# Mod_Matrix_Mixer_2x4x2.net
KiCad netlist of a schematic drawn in EAGLE
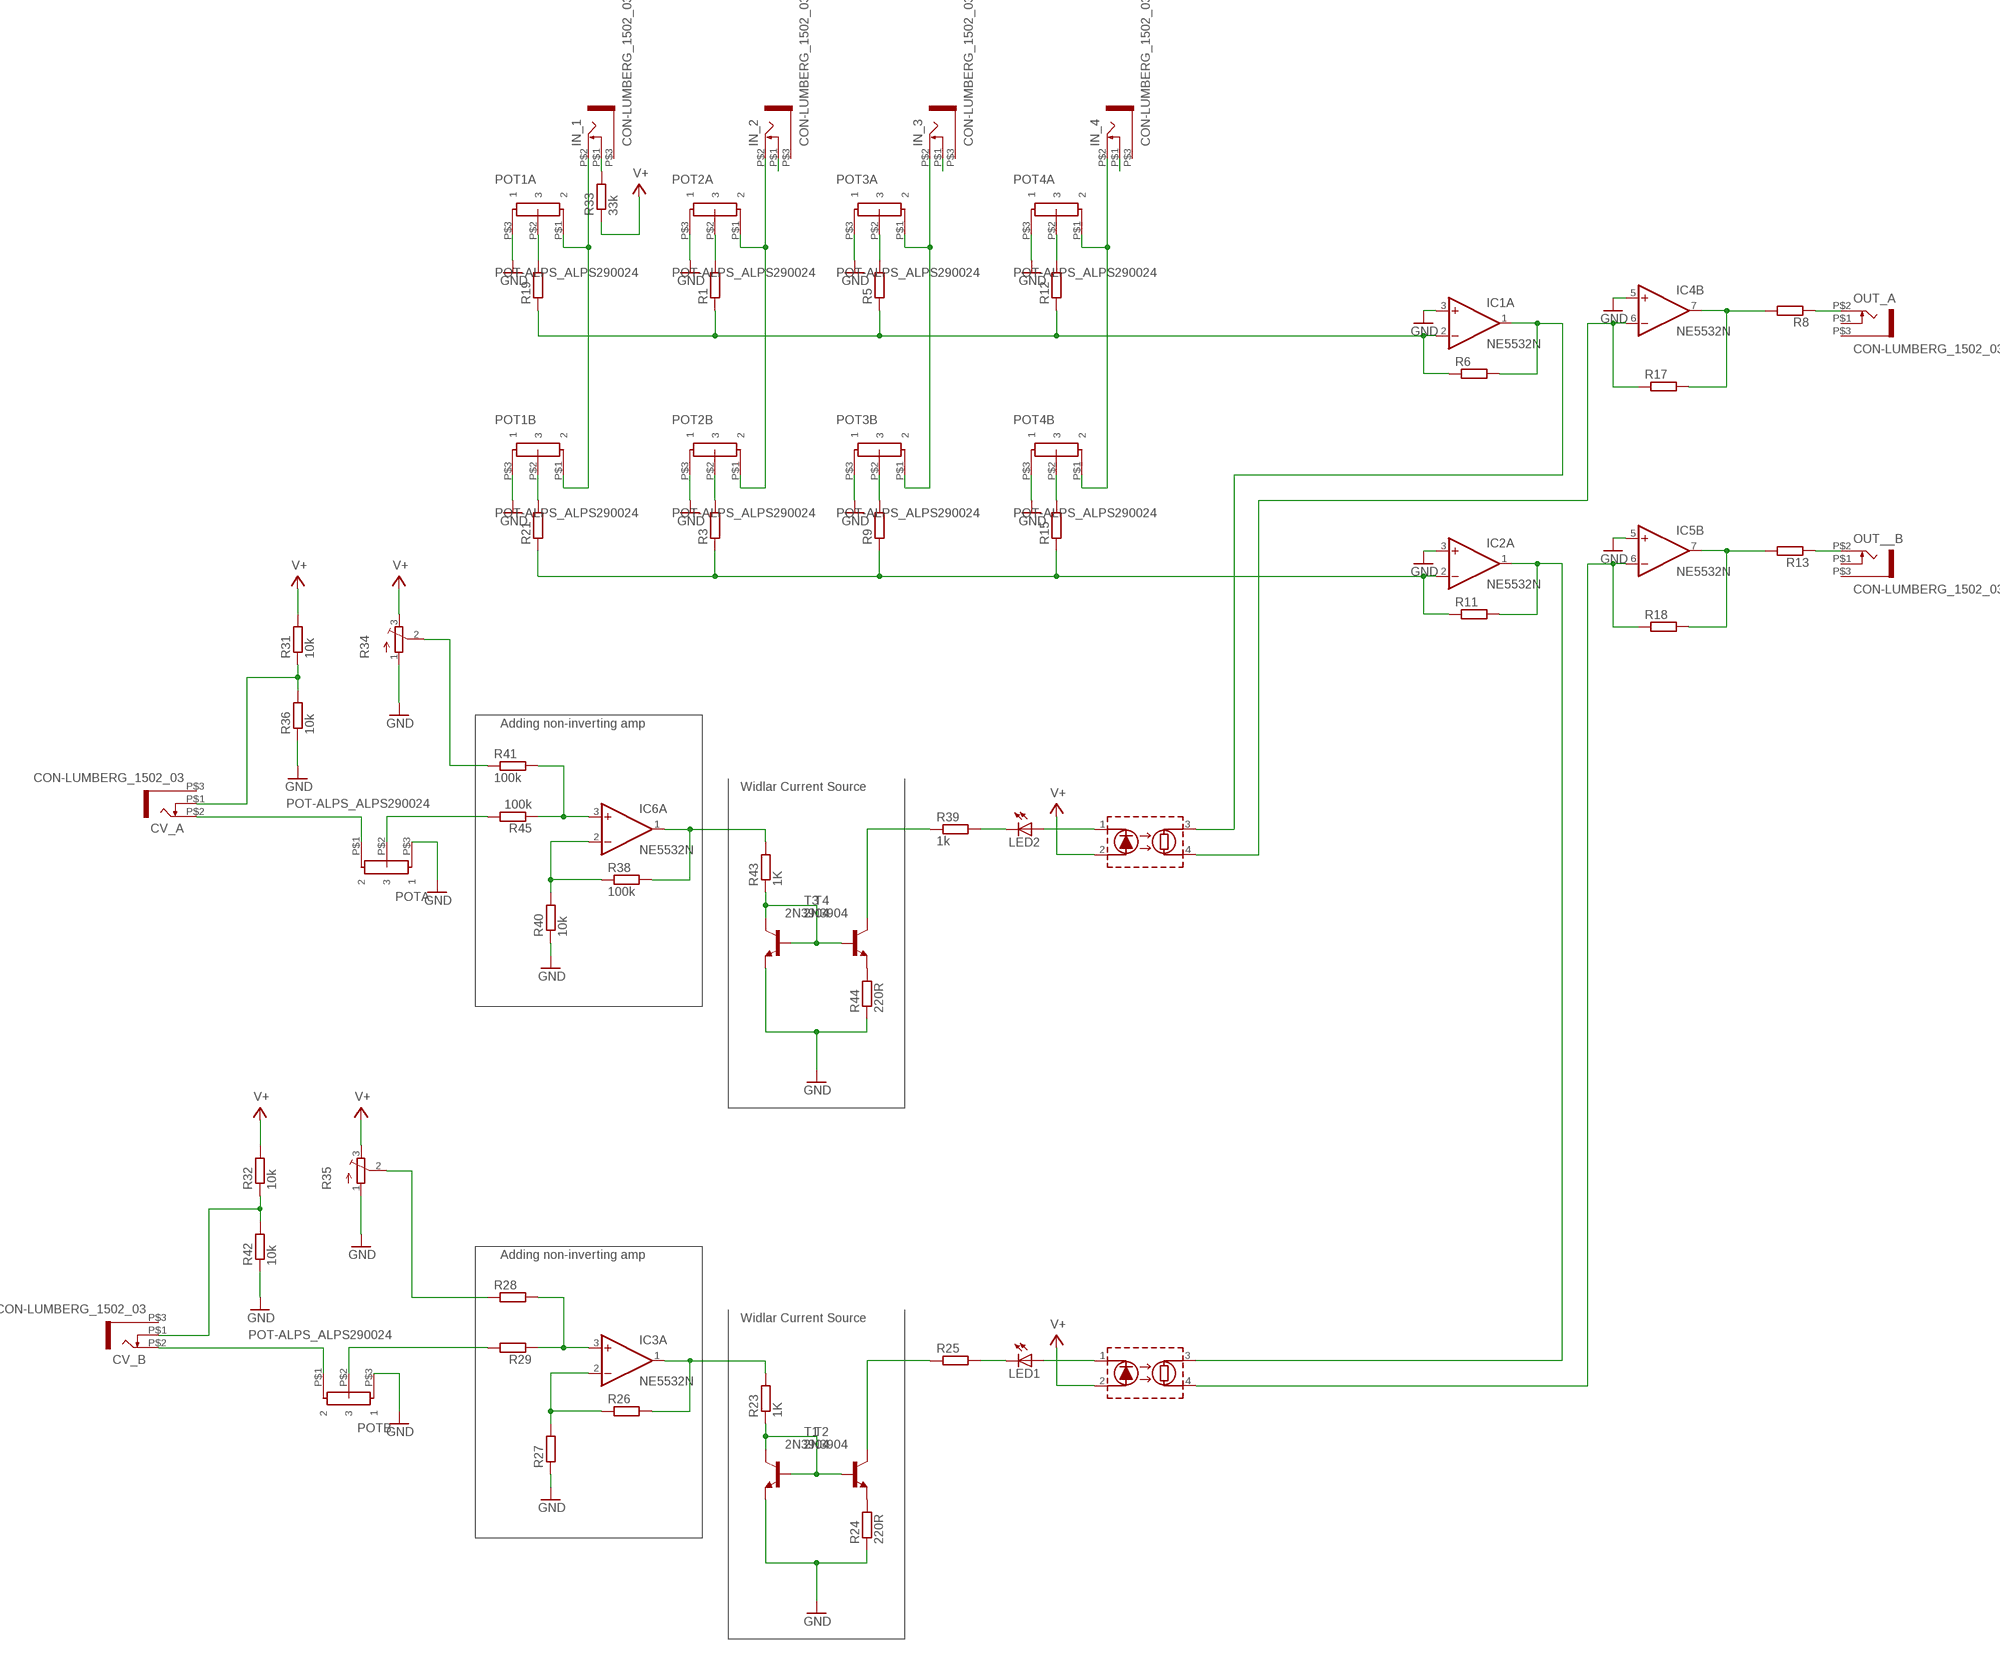
[diagram p0: schematic, sheet 1]

(export (version "E")
  (design (tool "Eeschema 10.0.6"))
  (components
    (comp (ref "CV_A")
      (value "CON-LUMBERG_1502_03")
      (footprint "eagle-import:CON-LUMBERG_1502_03")
      (libsource (lib "eagle-import") (part "CON-LUMBERG_1502_03"))
    )
    (comp (ref "CV_B")
      (value "CON-LUMBERG_1502_03")
      (footprint "eagle-import:CON-LUMBERG_1502_03")
      (libsource (lib "eagle-import") (part "CON-LUMBERG_1502_03"))
    )
    (comp (ref "IC1")
      (value "NE5532N")
      (footprint "eagle-import:DIL08")
      (libsource (lib "eagle-import") (part "NE5532N"))
    )
    (comp (ref "IC2")
      (value "NE5532N")
      (footprint "eagle-import:DIL08")
      (libsource (lib "eagle-import") (part "NE5532N"))
    )
    (comp (ref "IC3")
      (value "NE5532N")
      (footprint "eagle-import:DIL08")
      (libsource (lib "eagle-import") (part "NE5532N"))
    )
    (comp (ref "IC4")
      (value "NE5532N")
      (footprint "eagle-import:DIL08")
      (libsource (lib "eagle-import") (part "NE5532N"))
    )
    (comp (ref "IC5")
      (value "NE5532N")
      (footprint "eagle-import:DIL08")
      (libsource (lib "eagle-import") (part "NE5532N"))
    )
    (comp (ref "IC6")
      (value "NE5532N")
      (footprint "eagle-import:DIL08")
      (libsource (lib "eagle-import") (part "NE5532N"))
    )
    (comp (ref "IN_1")
      (value "CON-LUMBERG_1502_03")
      (footprint "eagle-import:CON-LUMBERG_1502_03")
      (libsource (lib "eagle-import") (part "CON-LUMBERG_1502_03"))
    )
    (comp (ref "IN_2")
      (value "CON-LUMBERG_1502_03")
      (footprint "eagle-import:CON-LUMBERG_1502_03")
      (libsource (lib "eagle-import") (part "CON-LUMBERG_1502_03"))
    )
    (comp (ref "IN_3")
      (value "CON-LUMBERG_1502_03")
      (footprint "eagle-import:CON-LUMBERG_1502_03")
      (libsource (lib "eagle-import") (part "CON-LUMBERG_1502_03"))
    )
    (comp (ref "IN_4")
      (value "CON-LUMBERG_1502_03")
      (footprint "eagle-import:CON-LUMBERG_1502_03")
      (libsource (lib "eagle-import") (part "CON-LUMBERG_1502_03"))
    )
    (comp (ref "LED1")
      (value "LED5MM")
      (footprint "eagle-import:LED5MM")
      (libsource (lib "eagle-import") (part "LED5MM"))
    )
    (comp (ref "LED2")
      (value "LED5MM")
      (footprint "eagle-import:LED5MM")
      (libsource (lib "eagle-import") (part "LED5MM"))
    )
    (comp (ref "OUT_A")
      (value "CON-LUMBERG_1502_03")
      (footprint "eagle-import:CON-LUMBERG_1502_03")
      (libsource (lib "eagle-import") (part "CON-LUMBERG_1502_03"))
    )
    (comp (ref "OUT__B")
      (value "CON-LUMBERG_1502_03")
      (footprint "eagle-import:CON-LUMBERG_1502_03")
      (libsource (lib "eagle-import") (part "CON-LUMBERG_1502_03"))
    )
    (comp (ref "POT1A")
      (value "POT-ALPS_ALPS290024")
      (footprint "eagle-import:POT-ALPS_POT")
      (libsource (lib "eagle-import") (part "POT-ALPS_ALPS290024"))
    )
    (comp (ref "POT1B")
      (value "POT-ALPS_ALPS290024")
      (footprint "eagle-import:POT-ALPS_POT")
      (libsource (lib "eagle-import") (part "POT-ALPS_ALPS290024"))
    )
    (comp (ref "POT2A")
      (value "POT-ALPS_ALPS290024")
      (footprint "eagle-import:POT-ALPS_POT")
      (libsource (lib "eagle-import") (part "POT-ALPS_ALPS290024"))
    )
    (comp (ref "POT2B")
      (value "POT-ALPS_ALPS290024")
      (footprint "eagle-import:POT-ALPS_POT")
      (libsource (lib "eagle-import") (part "POT-ALPS_ALPS290024"))
    )
    (comp (ref "POT3A")
      (value "POT-ALPS_ALPS290024")
      (footprint "eagle-import:POT-ALPS_POT")
      (libsource (lib "eagle-import") (part "POT-ALPS_ALPS290024"))
    )
    (comp (ref "POT3B")
      (value "POT-ALPS_ALPS290024")
      (footprint "eagle-import:POT-ALPS_POT")
      (libsource (lib "eagle-import") (part "POT-ALPS_ALPS290024"))
    )
    (comp (ref "POT4A")
      (value "POT-ALPS_ALPS290024")
      (footprint "eagle-import:POT-ALPS_POT")
      (libsource (lib "eagle-import") (part "POT-ALPS_ALPS290024"))
    )
    (comp (ref "POT4B")
      (value "POT-ALPS_ALPS290024")
      (footprint "eagle-import:POT-ALPS_POT")
      (libsource (lib "eagle-import") (part "POT-ALPS_ALPS290024"))
    )
    (comp (ref "POTA")
      (value "POT-ALPS_ALPS290024")
      (footprint "eagle-import:POT-ALPS_POT")
      (libsource (lib "eagle-import") (part "POT-ALPS_ALPS290024"))
    )
    (comp (ref "POTB")
      (value "POT-ALPS_ALPS290024")
      (footprint "eagle-import:POT-ALPS_POT")
      (libsource (lib "eagle-import") (part "POT-ALPS_ALPS290024"))
    )
    (comp (ref "R1")
      (value "R-EU_0411/15")
      (footprint "eagle-import:0411_15")
      (libsource (lib "eagle-import") (part "R-EU_0411/15"))
    )
    (comp (ref "R3")
      (value "R-EU_0411/15")
      (footprint "eagle-import:0411_15")
      (libsource (lib "eagle-import") (part "R-EU_0411/15"))
    )
    (comp (ref "R5")
      (value "R-EU_0411/15")
      (footprint "eagle-import:0411_15")
      (libsource (lib "eagle-import") (part "R-EU_0411/15"))
    )
    (comp (ref "R6")
      (value "R-EU_0411/15")
      (footprint "eagle-import:0411_15")
      (libsource (lib "eagle-import") (part "R-EU_0411/15"))
    )
    (comp (ref "R8")
      (value "R-EU_0411/15")
      (footprint "eagle-import:0411_15")
      (libsource (lib "eagle-import") (part "R-EU_0411/15"))
    )
    (comp (ref "R9")
      (value "R-EU_0411/15")
      (footprint "eagle-import:0411_15")
      (libsource (lib "eagle-import") (part "R-EU_0411/15"))
    )
    (comp (ref "R11")
      (value "R-EU_0411/15")
      (footprint "eagle-import:0411_15")
      (libsource (lib "eagle-import") (part "R-EU_0411/15"))
    )
    (comp (ref "R12")
      (value "R-EU_0411/15")
      (footprint "eagle-import:0411_15")
      (libsource (lib "eagle-import") (part "R-EU_0411/15"))
    )
    (comp (ref "R13")
      (value "R-EU_0411/15")
      (footprint "eagle-import:0411_15")
      (libsource (lib "eagle-import") (part "R-EU_0411/15"))
    )
    (comp (ref "R15")
      (value "R-EU_0411/15")
      (footprint "eagle-import:0411_15")
      (libsource (lib "eagle-import") (part "R-EU_0411/15"))
    )
    (comp (ref "R17")
      (value "R-EU_0411/15")
      (footprint "eagle-import:0411_15")
      (libsource (lib "eagle-import") (part "R-EU_0411/15"))
    )
    (comp (ref "R18")
      (value "R-EU_0411/15")
      (footprint "eagle-import:0411_15")
      (libsource (lib "eagle-import") (part "R-EU_0411/15"))
    )
    (comp (ref "R19")
      (value "R-EU_0411/15")
      (footprint "eagle-import:0411_15")
      (libsource (lib "eagle-import") (part "R-EU_0411/15"))
    )
    (comp (ref "R21")
      (value "R-EU_0411/15")
      (footprint "eagle-import:0411_15")
      (libsource (lib "eagle-import") (part "R-EU_0411/15"))
    )
    (comp (ref "R23")
      (value "1K")
      (footprint "eagle-import:0411_15")
      (libsource (lib "eagle-import") (part "R-EU_0411/15"))
    )
    (comp (ref "R24")
      (value "220R")
      (footprint "eagle-import:0411_15")
      (libsource (lib "eagle-import") (part "R-EU_0411/15"))
    )
    (comp (ref "R25")
      (value "R-EU_0411/15")
      (footprint "eagle-import:0411_15")
      (libsource (lib "eagle-import") (part "R-EU_0411/15"))
    )
    (comp (ref "R26")
      (value "R-EU_0411/15")
      (footprint "eagle-import:0411_15")
      (libsource (lib "eagle-import") (part "R-EU_0411/15"))
    )
    (comp (ref "R27")
      (value "R-EU_0411/15")
      (footprint "eagle-import:0411_15")
      (libsource (lib "eagle-import") (part "R-EU_0411/15"))
    )
    (comp (ref "R28")
      (value "R-EU_0411/15")
      (footprint "eagle-import:0411_15")
      (libsource (lib "eagle-import") (part "R-EU_0411/15"))
    )
    (comp (ref "R29")
      (value "R-EU_0411/15")
      (footprint "eagle-import:0411_15")
      (libsource (lib "eagle-import") (part "R-EU_0411/15"))
    )
    (comp (ref "R31")
      (value "10k")
      (footprint "eagle-import:0411_15")
      (libsource (lib "eagle-import") (part "R-EU_0411/15"))
    )
    (comp (ref "R32")
      (value "10k")
      (footprint "eagle-import:0411_15")
      (libsource (lib "eagle-import") (part "R-EU_0411/15"))
    )
    (comp (ref "R33")
      (value "33k")
      (footprint "eagle-import:0411_15")
      (libsource (lib "eagle-import") (part "R-EU_0411/15"))
    )
    (comp (ref "R34")
      (value "TRIM_EU-3223W")
      (footprint "eagle-import:3223W")
      (libsource (lib "eagle-import") (part "TRIM_EU-3223W"))
    )
    (comp (ref "R35")
      (value "TRIM_EU-3223W")
      (footprint "eagle-import:3223W")
      (libsource (lib "eagle-import") (part "TRIM_EU-3223W"))
    )
    (comp (ref "R36")
      (value "10k")
      (footprint "eagle-import:0411_15")
      (libsource (lib "eagle-import") (part "R-EU_0411/15"))
    )
    (comp (ref "R38")
      (value "100k")
      (footprint "eagle-import:0411_15")
      (libsource (lib "eagle-import") (part "R-EU_0411/15"))
    )
    (comp (ref "R39")
      (value "1k")
      (footprint "eagle-import:0411_15")
      (libsource (lib "eagle-import") (part "R-EU_0411/15"))
    )
    (comp (ref "R40")
      (value "10k")
      (footprint "eagle-import:0411_15")
      (libsource (lib "eagle-import") (part "R-EU_0411/15"))
    )
    (comp (ref "R41")
      (value "100k")
      (footprint "eagle-import:0411_15")
      (libsource (lib "eagle-import") (part "R-EU_0411/15"))
    )
    (comp (ref "R42")
      (value "10k")
      (footprint "eagle-import:0411_15")
      (libsource (lib "eagle-import") (part "R-EU_0411/15"))
    )
    (comp (ref "R43")
      (value "1K")
      (footprint "eagle-import:0411_15")
      (libsource (lib "eagle-import") (part "R-EU_0411/15"))
    )
    (comp (ref "R44")
      (value "220R")
      (footprint "eagle-import:0411_15")
      (libsource (lib "eagle-import") (part "R-EU_0411/15"))
    )
    (comp (ref "R45")
      (value "100k")
      (footprint "eagle-import:0411_15")
      (libsource (lib "eagle-import") (part "R-EU_0411/15"))
    )
    (comp (ref "T1")
      (value "2N3904")
      (footprint "eagle-import:TO92")
      (libsource (lib "eagle-import") (part "2N3904"))
    )
    (comp (ref "T2")
      (value "2N3904")
      (footprint "eagle-import:TO92")
      (libsource (lib "eagle-import") (part "2N3904"))
    )
    (comp (ref "T3")
      (value "2N3904")
      (footprint "eagle-import:TO92")
      (libsource (lib "eagle-import") (part "2N3904"))
    )
    (comp (ref "T4")
      (value "2N3904")
      (footprint "eagle-import:TO92")
      (libsource (lib "eagle-import") (part "2N3904"))
    )
    (comp (ref "U$1")
      (value "VTL5C3")
      (footprint "eagle-import:VTL5C3")
      (libsource (lib "eagle-import") (part "VTL5C3"))
    )
    (comp (ref "U$2")
      (value "VTL5C3")
      (footprint "eagle-import:VTL5C3")
      (libsource (lib "eagle-import") (part "VTL5C3"))
    )
  )
  (nets
    (net (code "1") (name "GND") (class "Default")
      (node (ref "IC1") (pin "3") (pinfunction "+IN_3") (pintype "input"))
      (node (ref "IC2") (pin "3") (pinfunction "+IN_3") (pintype "input"))
      (node (ref "IC4") (pin "5") (pinfunction "+IN_5") (pintype "input"))
      (node (ref "IC5") (pin "5") (pinfunction "+IN_5") (pintype "input"))
      (node (ref "POT1A") (pin "P$3") (pinfunction "1_P$3") (pintype "bidirectional"))
      (node (ref "POT1B") (pin "P$3") (pinfunction "1_P$3") (pintype "bidirectional"))
      (node (ref "POT2A") (pin "P$3") (pinfunction "1_P$3") (pintype "bidirectional"))
      (node (ref "POT2B") (pin "P$3") (pinfunction "1_P$3") (pintype "bidirectional"))
      (node (ref "POT3A") (pin "P$3") (pinfunction "1_P$3") (pintype "bidirectional"))
      (node (ref "POT3B") (pin "P$3") (pinfunction "1_P$3") (pintype "bidirectional"))
      (node (ref "POT4A") (pin "P$3") (pinfunction "1_P$3") (pintype "bidirectional"))
      (node (ref "POT4B") (pin "P$3") (pinfunction "1_P$3") (pintype "bidirectional"))
      (node (ref "POTA") (pin "P$3") (pinfunction "1_P$3") (pintype "bidirectional"))
      (node (ref "POTB") (pin "P$3") (pinfunction "1_P$3") (pintype "bidirectional"))
      (node (ref "R24") (pin "1") (pinfunction "1_1") (pintype "passive"))
      (node (ref "R27") (pin "1") (pinfunction "1_1") (pintype "passive"))
      (node (ref "R34") (pin "1") (pinfunction "A_1") (pintype "passive"))
      (node (ref "R35") (pin "1") (pinfunction "A_1") (pintype "passive"))
      (node (ref "R36") (pin "1") (pinfunction "1_1") (pintype "passive"))
      (node (ref "R40") (pin "1") (pinfunction "1_1") (pintype "passive"))
      (node (ref "R42") (pin "1") (pinfunction "1_1") (pintype "passive"))
      (node (ref "R44") (pin "1") (pinfunction "1_1") (pintype "passive"))
      (node (ref "T2") (pin "3") (pinfunction "E_3") (pintype "passive"))
      (node (ref "T4") (pin "3") (pinfunction "E_3") (pintype "passive"))
    )
    (net (code "2") (name "Net-(CV_A-3)") (class "Default")
      (node (ref "CV_A") (pin "P$2") (pinfunction "3_P$2") (pintype "passive"))
      (node (ref "POTA") (pin "P$1") (pinfunction "2_P$1") (pintype "bidirectional"))
    )
    (net (code "3") (name "Net-(CV_A-4)") (class "Default")
      (node (ref "CV_A") (pin "P$1") (pinfunction "4_P$1") (pintype "passive"))
      (node (ref "R31") (pin "1") (pinfunction "1_1") (pintype "passive"))
      (node (ref "R36") (pin "2") (pinfunction "2_2") (pintype "passive"))
    )
    (net (code "4") (name "Net-(CV_B-3)") (class "Default")
      (node (ref "CV_B") (pin "P$2") (pinfunction "3_P$2") (pintype "passive"))
      (node (ref "POTB") (pin "P$1") (pinfunction "2_P$1") (pintype "bidirectional"))
    )
    (net (code "5") (name "Net-(CV_B-4)") (class "Default")
      (node (ref "CV_B") (pin "P$1") (pinfunction "4_P$1") (pintype "passive"))
      (node (ref "R32") (pin "1") (pinfunction "1_1") (pintype "passive"))
      (node (ref "R42") (pin "2") (pinfunction "2_2") (pintype "passive"))
    )
    (net (code "6") (name "Net-(IC1A--IN)") (class "Default")
      (node (ref "IC1") (pin "2") (pinfunction "-IN_2") (pintype "input"))
      (node (ref "R1") (pin "1") (pinfunction "1_1") (pintype "passive"))
      (node (ref "R12") (pin "1") (pinfunction "1_1") (pintype "passive"))
      (node (ref "R19") (pin "1") (pinfunction "1_1") (pintype "passive"))
      (node (ref "R5") (pin "1") (pinfunction "1_1") (pintype "passive"))
      (node (ref "R6") (pin "1") (pinfunction "1_1") (pintype "passive"))
    )
    (net (code "7") (name "Net-(IC1A-OUT)") (class "Default")
      (node (ref "IC1") (pin "1") (pinfunction "OUT_1") (pintype "output"))
      (node (ref "R6") (pin "2") (pinfunction "2_2") (pintype "passive"))
      (node (ref "U$2") (pin "3") (pinfunction "LDRA_3") (pintype "bidirectional"))
    )
    (net (code "8") (name "Net-(IC2A--IN)") (class "Default")
      (node (ref "IC2") (pin "2") (pinfunction "-IN_2") (pintype "input"))
      (node (ref "R11") (pin "1") (pinfunction "1_1") (pintype "passive"))
      (node (ref "R15") (pin "1") (pinfunction "1_1") (pintype "passive"))
      (node (ref "R21") (pin "1") (pinfunction "1_1") (pintype "passive"))
      (node (ref "R3") (pin "1") (pinfunction "1_1") (pintype "passive"))
      (node (ref "R9") (pin "1") (pinfunction "1_1") (pintype "passive"))
    )
    (net (code "9") (name "Net-(IC2A-OUT)") (class "Default")
      (node (ref "IC2") (pin "1") (pinfunction "OUT_1") (pintype "output"))
      (node (ref "R11") (pin "2") (pinfunction "2_2") (pintype "passive"))
      (node (ref "U$1") (pin "3") (pinfunction "LDRA_3") (pintype "bidirectional"))
    )
    (net (code "10") (name "Net-(IC3A-+IN)") (class "Default")
      (node (ref "IC3") (pin "3") (pinfunction "+IN_3") (pintype "input"))
      (node (ref "R28") (pin "2") (pinfunction "2_2") (pintype "passive"))
      (node (ref "R29") (pin "1") (pinfunction "1_1") (pintype "passive"))
    )
    (net (code "11") (name "Net-(IC3A--IN)") (class "Default")
      (node (ref "IC3") (pin "2") (pinfunction "-IN_2") (pintype "input"))
      (node (ref "R26") (pin "1") (pinfunction "1_1") (pintype "passive"))
      (node (ref "R27") (pin "2") (pinfunction "2_2") (pintype "passive"))
    )
    (net (code "12") (name "Net-(IC3A-OUT)") (class "Default")
      (node (ref "IC3") (pin "1") (pinfunction "OUT_1") (pintype "output"))
      (node (ref "R23") (pin "2") (pinfunction "2_2") (pintype "passive"))
      (node (ref "R26") (pin "2") (pinfunction "2_2") (pintype "passive"))
    )
    (net (code "13") (name "Net-(IC4B--IN)") (class "Default")
      (node (ref "IC4") (pin "6") (pinfunction "-IN_6") (pintype "input"))
      (node (ref "R17") (pin "1") (pinfunction "1_1") (pintype "passive"))
      (node (ref "U$2") (pin "4") (pinfunction "LDRB_4") (pintype "bidirectional"))
    )
    (net (code "14") (name "Net-(IC4B-OUT)") (class "Default")
      (node (ref "IC4") (pin "7") (pinfunction "OUT_7") (pintype "output"))
      (node (ref "R17") (pin "2") (pinfunction "2_2") (pintype "passive"))
      (node (ref "R8") (pin "2") (pinfunction "2_2") (pintype "passive"))
    )
    (net (code "15") (name "Net-(IC5B--IN)") (class "Default")
      (node (ref "IC5") (pin "6") (pinfunction "-IN_6") (pintype "input"))
      (node (ref "R18") (pin "1") (pinfunction "1_1") (pintype "passive"))
      (node (ref "U$1") (pin "4") (pinfunction "LDRB_4") (pintype "bidirectional"))
    )
    (net (code "16") (name "Net-(IC5B-OUT)") (class "Default")
      (node (ref "IC5") (pin "7") (pinfunction "OUT_7") (pintype "output"))
      (node (ref "R13") (pin "2") (pinfunction "2_2") (pintype "passive"))
      (node (ref "R18") (pin "2") (pinfunction "2_2") (pintype "passive"))
    )
    (net (code "17") (name "Net-(IC6A-+IN)") (class "Default")
      (node (ref "IC6") (pin "3") (pinfunction "+IN_3") (pintype "input"))
      (node (ref "R41") (pin "2") (pinfunction "2_2") (pintype "passive"))
      (node (ref "R45") (pin "1") (pinfunction "1_1") (pintype "passive"))
    )
    (net (code "18") (name "Net-(IC6A--IN)") (class "Default")
      (node (ref "IC6") (pin "2") (pinfunction "-IN_2") (pintype "input"))
      (node (ref "R38") (pin "1") (pinfunction "1_1") (pintype "passive"))
      (node (ref "R40") (pin "2") (pinfunction "2_2") (pintype "passive"))
    )
    (net (code "19") (name "Net-(IC6A-OUT)") (class "Default")
      (node (ref "IC6") (pin "1") (pinfunction "OUT_1") (pintype "output"))
      (node (ref "R38") (pin "2") (pinfunction "2_2") (pintype "passive"))
      (node (ref "R43") (pin "2") (pinfunction "2_2") (pintype "passive"))
    )
    (net (code "20") (name "Net-(IN_1-3)") (class "Default")
      (node (ref "IN_1") (pin "P$2") (pinfunction "3_P$2") (pintype "passive"))
      (node (ref "POT1A") (pin "P$1") (pinfunction "2_P$1") (pintype "bidirectional"))
      (node (ref "POT1B") (pin "P$1") (pinfunction "2_P$1") (pintype "bidirectional"))
    )
    (net (code "21") (name "Net-(IN_1-4)") (class "Default")
      (node (ref "IN_1") (pin "P$1") (pinfunction "4_P$1") (pintype "passive"))
      (node (ref "R33") (pin "2") (pinfunction "2_2") (pintype "passive"))
    )
    (net (code "22") (name "Net-(IN_2-3)") (class "Default")
      (node (ref "IN_2") (pin "P$2") (pinfunction "3_P$2") (pintype "passive"))
      (node (ref "POT2A") (pin "P$1") (pinfunction "2_P$1") (pintype "bidirectional"))
      (node (ref "POT2B") (pin "P$1") (pinfunction "2_P$1") (pintype "bidirectional"))
    )
    (net (code "23") (name "Net-(IN_3-3)") (class "Default")
      (node (ref "IN_3") (pin "P$2") (pinfunction "3_P$2") (pintype "passive"))
      (node (ref "POT3A") (pin "P$1") (pinfunction "2_P$1") (pintype "bidirectional"))
      (node (ref "POT3B") (pin "P$1") (pinfunction "2_P$1") (pintype "bidirectional"))
    )
    (net (code "24") (name "Net-(IN_4-3)") (class "Default")
      (node (ref "IN_4") (pin "P$2") (pinfunction "3_P$2") (pintype "passive"))
      (node (ref "POT4A") (pin "P$1") (pinfunction "2_P$1") (pintype "bidirectional"))
      (node (ref "POT4B") (pin "P$1") (pinfunction "2_P$1") (pintype "bidirectional"))
    )
    (net (code "25") (name "Net-(LED1-C)") (class "Default")
      (node (ref "LED1") (pin "K") (pinfunction "C_K") (pintype "passive"))
      (node (ref "R25") (pin "2") (pinfunction "2_2") (pintype "passive"))
    )
    (net (code "26") (name "Net-(LED2-C)") (class "Default")
      (node (ref "LED2") (pin "K") (pinfunction "C_K") (pintype "passive"))
      (node (ref "R39") (pin "2") (pinfunction "2_2") (pintype "passive"))
    )
    (net (code "27") (name "Net-(OUT_A-3)") (class "Default")
      (node (ref "OUT_A") (pin "P$2") (pinfunction "3_P$2") (pintype "passive"))
      (node (ref "R8") (pin "1") (pinfunction "1_1") (pintype "passive"))
    )
    (net (code "28") (name "Net-(OUT__B-3)") (class "Default")
      (node (ref "OUT__B") (pin "P$2") (pinfunction "3_P$2") (pintype "passive"))
      (node (ref "R13") (pin "1") (pinfunction "1_1") (pintype "passive"))
    )
    (net (code "29") (name "Net-(POT1A-3)") (class "Default")
      (node (ref "POT1A") (pin "P$2") (pinfunction "3_P$2") (pintype "bidirectional"))
      (node (ref "R19") (pin "2") (pinfunction "2_2") (pintype "passive"))
    )
    (net (code "30") (name "Net-(POT1B-3)") (class "Default")
      (node (ref "POT1B") (pin "P$2") (pinfunction "3_P$2") (pintype "bidirectional"))
      (node (ref "R21") (pin "2") (pinfunction "2_2") (pintype "passive"))
    )
    (net (code "31") (name "Net-(POT2A-3)") (class "Default")
      (node (ref "POT2A") (pin "P$2") (pinfunction "3_P$2") (pintype "bidirectional"))
      (node (ref "R1") (pin "2") (pinfunction "2_2") (pintype "passive"))
    )
    (net (code "32") (name "Net-(POT2B-3)") (class "Default")
      (node (ref "POT2B") (pin "P$2") (pinfunction "3_P$2") (pintype "bidirectional"))
      (node (ref "R3") (pin "2") (pinfunction "2_2") (pintype "passive"))
    )
    (net (code "33") (name "Net-(POT3A-3)") (class "Default")
      (node (ref "POT3A") (pin "P$2") (pinfunction "3_P$2") (pintype "bidirectional"))
      (node (ref "R5") (pin "2") (pinfunction "2_2") (pintype "passive"))
    )
    (net (code "34") (name "Net-(POT3B-3)") (class "Default")
      (node (ref "POT3B") (pin "P$2") (pinfunction "3_P$2") (pintype "bidirectional"))
      (node (ref "R9") (pin "2") (pinfunction "2_2") (pintype "passive"))
    )
    (net (code "35") (name "Net-(POT4A-3)") (class "Default")
      (node (ref "POT4A") (pin "P$2") (pinfunction "3_P$2") (pintype "bidirectional"))
      (node (ref "R12") (pin "2") (pinfunction "2_2") (pintype "passive"))
    )
    (net (code "36") (name "Net-(POT4B-3)") (class "Default")
      (node (ref "POT4B") (pin "P$2") (pinfunction "3_P$2") (pintype "bidirectional"))
      (node (ref "R15") (pin "2") (pinfunction "2_2") (pintype "passive"))
    )
    (net (code "37") (name "Net-(POTA-3)") (class "Default")
      (node (ref "POTA") (pin "P$2") (pinfunction "3_P$2") (pintype "bidirectional"))
      (node (ref "R45") (pin "2") (pinfunction "2_2") (pintype "passive"))
    )
    (net (code "38") (name "Net-(POTB-3)") (class "Default")
      (node (ref "POTB") (pin "P$2") (pinfunction "3_P$2") (pintype "bidirectional"))
      (node (ref "R29") (pin "2") (pinfunction "2_2") (pintype "passive"))
    )
    (net (code "39") (name "Net-(R34-S)") (class "Default")
      (node (ref "R34") (pin "2") (pinfunction "S_2") (pintype "passive"))
      (node (ref "R41") (pin "1") (pinfunction "1_1") (pintype "passive"))
    )
    (net (code "40") (name "Net-(R35-S)") (class "Default")
      (node (ref "R28") (pin "1") (pinfunction "1_1") (pintype "passive"))
      (node (ref "R35") (pin "2") (pinfunction "S_2") (pintype "passive"))
    )
    (net (code "41") (name "Net-(T1-B)") (class "Default")
      (node (ref "R23") (pin "1") (pinfunction "1_1") (pintype "passive"))
      (node (ref "T1") (pin "2") (pinfunction "B_2") (pintype "passive"))
      (node (ref "T2") (pin "1") (pinfunction "C_1") (pintype "passive"))
      (node (ref "T2") (pin "2") (pinfunction "B_2") (pintype "passive"))
    )
    (net (code "42") (name "Net-(T1-C)") (class "Default")
      (node (ref "R25") (pin "1") (pinfunction "1_1") (pintype "passive"))
      (node (ref "T1") (pin "1") (pinfunction "C_1") (pintype "passive"))
    )
    (net (code "43") (name "Net-(T1-E)") (class "Default")
      (node (ref "R24") (pin "2") (pinfunction "2_2") (pintype "passive"))
      (node (ref "T1") (pin "3") (pinfunction "E_3") (pintype "passive"))
    )
    (net (code "44") (name "Net-(T3-B)") (class "Default")
      (node (ref "R43") (pin "1") (pinfunction "1_1") (pintype "passive"))
      (node (ref "T3") (pin "2") (pinfunction "B_2") (pintype "passive"))
      (node (ref "T4") (pin "1") (pinfunction "C_1") (pintype "passive"))
      (node (ref "T4") (pin "2") (pinfunction "B_2") (pintype "passive"))
    )
    (net (code "45") (name "Net-(T3-C)") (class "Default")
      (node (ref "R39") (pin "1") (pinfunction "1_1") (pintype "passive"))
      (node (ref "T3") (pin "1") (pinfunction "C_1") (pintype "passive"))
    )
    (net (code "46") (name "Net-(T3-E)") (class "Default")
      (node (ref "R44") (pin "2") (pinfunction "2_2") (pintype "passive"))
      (node (ref "T3") (pin "3") (pinfunction "E_3") (pintype "passive"))
    )
    (net (code "47") (name "Net-(U$1-LED-)") (class "Default")
      (node (ref "LED1") (pin "A") (pinfunction "A_A") (pintype "passive"))
      (node (ref "U$1") (pin "1") (pinfunction "LED-_1") (pintype "bidirectional"))
    )
    (net (code "48") (name "Net-(U$2-LED-)") (class "Default")
      (node (ref "LED2") (pin "A") (pinfunction "A_A") (pintype "passive"))
      (node (ref "U$2") (pin "1") (pinfunction "LED-_1") (pintype "bidirectional"))
    )
    (net (code "49") (name "V+") (class "Default")
      (node (ref "R31") (pin "2") (pinfunction "2_2") (pintype "passive"))
      (node (ref "R32") (pin "2") (pinfunction "2_2") (pintype "passive"))
      (node (ref "R33") (pin "1") (pinfunction "1_1") (pintype "passive"))
      (node (ref "R34") (pin "3") (pinfunction "E_3") (pintype "passive"))
      (node (ref "R35") (pin "3") (pinfunction "E_3") (pintype "passive"))
      (node (ref "U$1") (pin "2") (pinfunction "LED+_2") (pintype "bidirectional"))
      (node (ref "U$2") (pin "2") (pinfunction "LED+_2") (pintype "bidirectional"))
    )
    (net (code "50") (name "unconnected-(CV_A-5-PadP$3)") (class "Default")
      (node (ref "CV_A") (pin "P$3") (pinfunction "5_P$3") (pintype "passive"))
    )
    (net (code "51") (name "unconnected-(CV_B-5-PadP$3)") (class "Default")
      (node (ref "CV_B") (pin "P$3") (pinfunction "5_P$3") (pintype "passive"))
    )
    (net (code "52") (name "unconnected-(IN_1-5-PadP$3)") (class "Default")
      (node (ref "IN_1") (pin "P$3") (pinfunction "5_P$3") (pintype "passive"))
    )
    (net (code "53") (name "unconnected-(IN_2-4-PadP$1)") (class "Default")
      (node (ref "IN_2") (pin "P$1") (pinfunction "4_P$1") (pintype "passive"))
    )
    (net (code "54") (name "unconnected-(IN_2-5-PadP$3)") (class "Default")
      (node (ref "IN_2") (pin "P$3") (pinfunction "5_P$3") (pintype "passive"))
    )
    (net (code "55") (name "unconnected-(IN_3-4-PadP$1)") (class "Default")
      (node (ref "IN_3") (pin "P$1") (pinfunction "4_P$1") (pintype "passive"))
    )
    (net (code "56") (name "unconnected-(IN_3-5-PadP$3)") (class "Default")
      (node (ref "IN_3") (pin "P$3") (pinfunction "5_P$3") (pintype "passive"))
    )
    (net (code "57") (name "unconnected-(IN_4-4-PadP$1)") (class "Default")
      (node (ref "IN_4") (pin "P$1") (pinfunction "4_P$1") (pintype "passive"))
    )
    (net (code "58") (name "unconnected-(IN_4-5-PadP$3)") (class "Default")
      (node (ref "IN_4") (pin "P$3") (pinfunction "5_P$3") (pintype "passive"))
    )
    (net (code "59") (name "unconnected-(OUT_A-4-PadP$1)") (class "Default")
      (node (ref "OUT_A") (pin "P$1") (pinfunction "4_P$1") (pintype "passive"))
    )
    (net (code "60") (name "unconnected-(OUT_A-5-PadP$3)") (class "Default")
      (node (ref "OUT_A") (pin "P$3") (pinfunction "5_P$3") (pintype "passive"))
    )
    (net (code "61") (name "unconnected-(OUT__B-4-PadP$1)") (class "Default")
      (node (ref "OUT__B") (pin "P$1") (pinfunction "4_P$1") (pintype "passive"))
    )
    (net (code "62") (name "unconnected-(OUT__B-5-PadP$3)") (class "Default")
      (node (ref "OUT__B") (pin "P$3") (pinfunction "5_P$3") (pintype "passive"))
    )
  )
)
